# Peripheral_Connections.net
KiCad netlist of a schematic drawn in Altium Designer
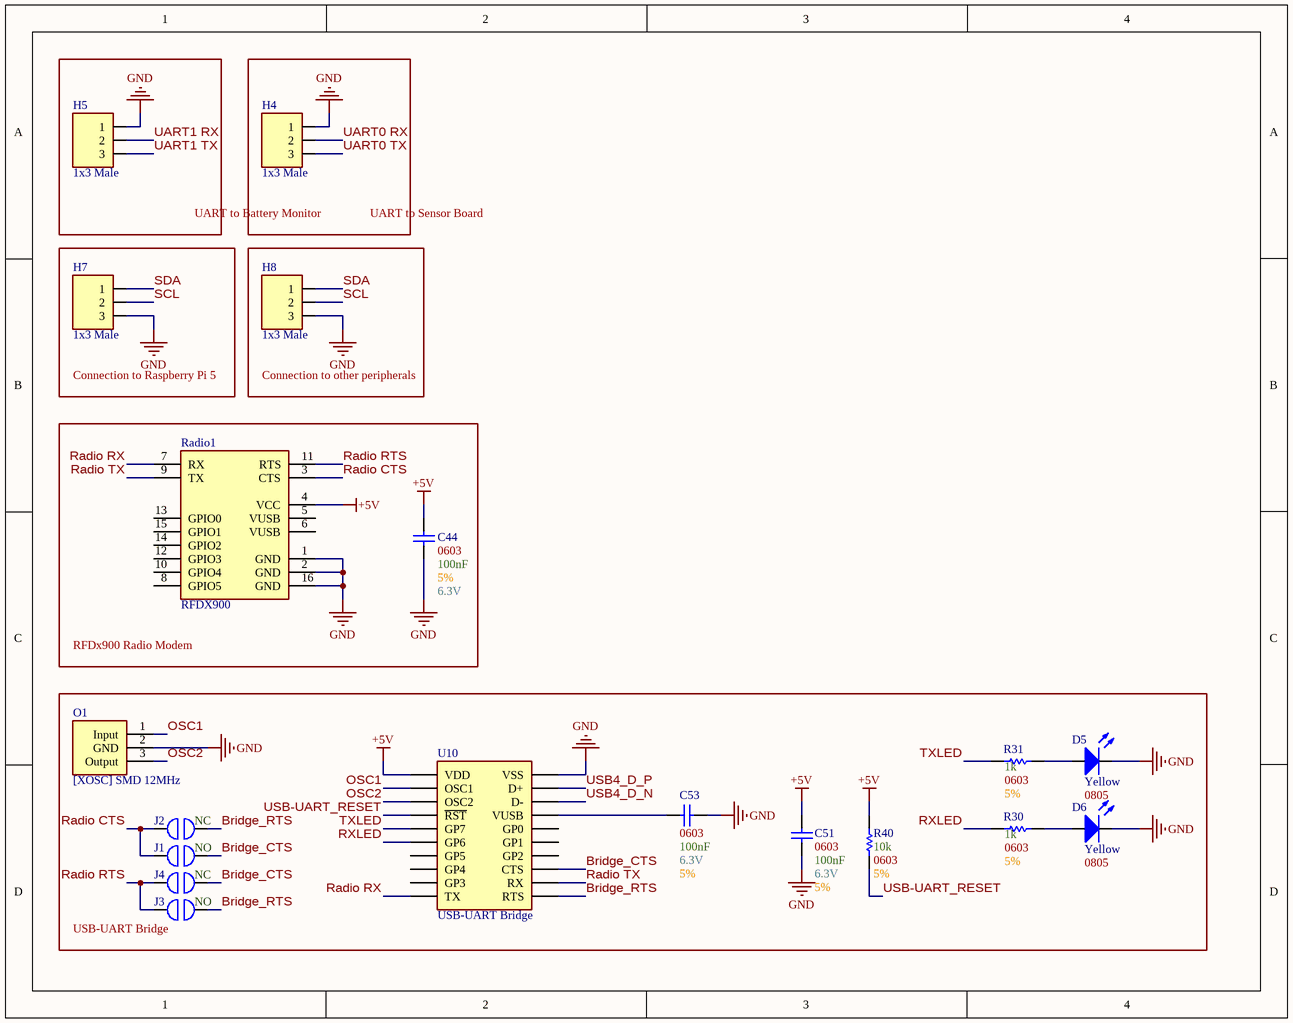
[diagram p0: Peripheral Connections.SchDoc]

(export (version "E")
  (design (tool "Eeschema 10.0.6"))
  (components
    (comp (ref "C44")
      (value "[Cap] SMD Nonpolarized")
      (footprint "[Cap] SMD 0603")
      (fields
        (field (name "SIZE PACKAGE") "0603")
        (field (name "CAPACITANCE") "100nF")
        (field (name "VOLTAGE") "6.3V")
        (field (name "TOLERANCE") "5%")
      )
      (libsource (lib "RADM Components") (part "[Cap] SMD Nonpolarized"))
    )
    (comp (ref "C51")
      (value "[Cap] SMD Nonpolarized")
      (footprint "[Cap] SMD 0603")
      (fields
        (field (name "SIZE PACKAGE") "0603")
        (field (name "CAPACITANCE") "100nF")
        (field (name "VOLTAGE") "6.3V")
        (field (name "TOLERANCE") "5%")
      )
      (libsource (lib "RADM Components") (part "[Cap] SMD Nonpolarized"))
    )
    (comp (ref "C53")
      (value "[Cap] SMD Nonpolarized")
      (footprint "[Cap] SMD 0603")
      (fields
        (field (name "SIZE PACKAGE") "0603")
        (field (name "CAPACITANCE") "100nF")
        (field (name "VOLTAGE") "6.3V")
        (field (name "TOLERANCE") "5%")
      )
      (libsource (lib "RADM Components") (part "[Cap] SMD Nonpolarized"))
    )
    (comp (ref "D5")
      (value "SMD LED")
      (footprint "[LED] SMD 0805")
      (description "Generic")
      (fields (field (name "COLOR") "Yellow") (field (name "SIZE PACKAGE") "0805"))
      (libsource (lib "RADM Components") (part "[LED] SMD"))
    )
    (comp (ref "D6")
      (value "SMD LED")
      (footprint "[LED] SMD 0805")
      (description "Generic")
      (fields (field (name "COLOR") "Yellow") (field (name "SIZE PACKAGE") "0805"))
      (libsource (lib "RADM Components") (part "[LED] SMD"))
    )
    (comp (ref "H4")
      (value "1x3 Male")
      (footprint "[Header] Shrouded 1x3 Male")
      (description "070543-0037\r\nMates with 005057-9403")
      (libsource (lib "RADM Connectors") (part "[Header] Shrouded 1x3 Male"))
    )
    (comp (ref "H5")
      (value "1x3 Male")
      (footprint "[Header] Shrouded 1x3 Male")
      (description "070543-0037\r\nMates with 005057-9403")
      (libsource (lib "RADM Connectors") (part "[Header] Shrouded 1x3 Male"))
    )
    (comp (ref "H7")
      (value "1x3 Male")
      (footprint "[Header] Shrouded 1x3 Male")
      (description "070543-0037\r\nMates with 005057-9403")
      (libsource (lib "RADM Connectors") (part "[Header] Shrouded 1x3 Male"))
    )
    (comp (ref "H8")
      (value "1x3 Male")
      (footprint "[Header] Shrouded 1x3 Male")
      (description "070543-0037\r\nMates with 005057-9403")
      (libsource (lib "RADM Connectors") (part "[Header] Shrouded 1x3 Male"))
    )
    (comp (ref "J1")
      (value "[Jump] SMD Jumper")
      (footprint "[Jumper] Solderable Jumper")
      (description "Solderable jumper")
      (fields (field (name "NO/NC") "NO"))
      (libsource (lib "RADM Components") (part "[Jump] SMD Jumper"))
    )
    (comp (ref "J2")
      (value "[Jump] SMD Jumper")
      (footprint "[Jumper] Solderable Jumper")
      (description "Solderable jumper")
      (fields (field (name "NO/NC") "NC"))
      (libsource (lib "RADM Components") (part "[Jump] SMD Jumper"))
    )
    (comp (ref "J3")
      (value "[Jump] SMD Jumper")
      (footprint "[Jumper] Solderable Jumper")
      (description "Solderable jumper")
      (fields (field (name "NO/NC") "NO"))
      (libsource (lib "RADM Components") (part "[Jump] SMD Jumper"))
    )
    (comp (ref "J4")
      (value "[Jump] SMD Jumper")
      (footprint "[Jumper] Solderable Jumper")
      (description "Solderable jumper")
      (fields (field (name "NO/NC") "NC"))
      (libsource (lib "RADM Components") (part "[Jump] SMD Jumper"))
    )
    (comp (ref "O1")
      (value "[XOSC] SMD 12MHz")
      (footprint "[XOSC] SMD 12MHz")
      (libsource (lib "RADM Components") (part "[XOSC] SMD 12MHz"))
    )
    (comp (ref "R30")
      (value "[Res] SMD Resistor")
      (footprint "[Res] SMD 0603")
      (description "Generic")
      (fields
        (field (name "RESISTANCE") "1k")
        (field (name "SIZE PACKAGE") "0603")
        (field (name "TOLERANCE") "5%")
      )
      (libsource (lib "RADM Components") (part "[Res] SMD Resistor"))
    )
    (comp (ref "R31")
      (value "[Res] SMD Resistor")
      (footprint "[Res] SMD 0603")
      (description "Generic")
      (fields
        (field (name "RESISTANCE") "1k")
        (field (name "SIZE PACKAGE") "0603")
        (field (name "TOLERANCE") "5%")
      )
      (libsource (lib "RADM Components") (part "[Res] SMD Resistor"))
    )
    (comp (ref "R40")
      (value "[Res] SMD Resistor")
      (footprint "[Res] SMD 0603")
      (description "Generic")
      (fields
        (field (name "RESISTANCE") "10k")
        (field (name "SIZE PACKAGE") "0603")
        (field (name "TOLERANCE") "5%")
      )
      (libsource (lib "RADM Components") (part "[Res] SMD Resistor"))
    )
    (comp (ref "Radio1")
      (value "RFDX900")
      (footprint "[Device] RFDX900 Radio SMD Mount")
      (description "RFDX900 Long-Range RF Module")
      (libsource (lib "RADM Components") (part "[Device] RFDX900 Radio"))
    )
    (comp (ref "U10")
      (value "USB-UART Bridge")
      (footprint "[IC] USB-UART Bridge")
      (description "MCP2200T-I/SO")
      (libsource (lib "RADM Components") (part "[IC] USB-UART Bridge"))
    )
  )
  (nets
    (net (code "1") (name "+5V") (class "Default")
      (node (ref "C44") (pin "2") (pinfunction "2_2") (pintype "passive"))
      (node (ref "C51") (pin "2") (pinfunction "2_2") (pintype "passive"))
      (node (ref "R40") (pin "2") (pinfunction "2_2") (pintype "passive"))
      (node (ref "Radio1") (pin "4") (pinfunction "VCC_4") (pintype "passive"))
      (node (ref "U10") (pin "1") (pinfunction "VDD_1") (pintype "passive"))
    )
    (net (code "2") (name "/Bridge_CTS") (class "Default")
      (node (ref "J1") (pin "2") (pintype "passive"))
      (node (ref "J4") (pin "2") (pintype "passive"))
      (node (ref "U10") (pin "13") (pinfunction "CTS_13") (pintype "passive"))
    )
    (net (code "3") (name "/Bridge_RTS") (class "Default")
      (node (ref "J2") (pin "2") (pintype "passive"))
      (node (ref "J3") (pin "2") (pintype "passive"))
      (node (ref "U10") (pin "11") (pinfunction "RTS_11") (pintype "passive"))
    )
    (net (code "4") (name "/OSC1") (class "Default")
      (node (ref "O1") (pin "1") (pinfunction "Input_1") (pintype "passive"))
      (node (ref "U10") (pin "2") (pinfunction "OSC1_2") (pintype "passive"))
    )
    (net (code "5") (name "/OSC2") (class "Default")
      (node (ref "O1") (pin "3") (pinfunction "Output_3") (pintype "passive"))
      (node (ref "U10") (pin "3") (pinfunction "OSC2_3") (pintype "passive"))
    )
    (net (code "6") (name "/RXLED") (class "Default")
      (node (ref "R30") (pin "2") (pinfunction "2_2") (pintype "passive"))
      (node (ref "U10") (pin "6") (pinfunction "GP6_6") (pintype "passive"))
    )
    (net (code "7") (name "/Radio CTS") (class "Default")
      (node (ref "J1") (pin "1") (pintype "passive"))
      (node (ref "J2") (pin "1") (pintype "passive"))
      (node (ref "Radio1") (pin "3") (pinfunction "CTS_3") (pintype "passive"))
    )
    (net (code "8") (name "/Radio RTS") (class "Default")
      (node (ref "J3") (pin "1") (pintype "passive"))
      (node (ref "J4") (pin "1") (pintype "passive"))
      (node (ref "Radio1") (pin "11") (pinfunction "RTS_11") (pintype "passive"))
    )
    (net (code "9") (name "/Radio RX") (class "Default")
      (node (ref "Radio1") (pin "7") (pinfunction "RX_7") (pintype "passive"))
      (node (ref "U10") (pin "10") (pinfunction "TX_10") (pintype "passive"))
    )
    (net (code "10") (name "/Radio TX") (class "Default")
      (node (ref "Radio1") (pin "9") (pinfunction "TX_9") (pintype "passive"))
      (node (ref "U10") (pin "12") (pinfunction "RX_12") (pintype "passive"))
    )
    (net (code "11") (name "/SCL") (class "Default")
      (node (ref "H7") (pin "2") (pinfunction "2_2") (pintype "passive"))
      (node (ref "H8") (pin "2") (pinfunction "2_2") (pintype "passive"))
    )
    (net (code "12") (name "/SDA") (class "Default")
      (node (ref "H7") (pin "1") (pinfunction "1_1") (pintype "passive"))
      (node (ref "H8") (pin "1") (pinfunction "1_1") (pintype "passive"))
    )
    (net (code "13") (name "/TXLED") (class "Default")
      (node (ref "R31") (pin "2") (pinfunction "2_2") (pintype "passive"))
      (node (ref "U10") (pin "5") (pinfunction "GP7_5") (pintype "passive"))
    )
    (net (code "14") (name "/UART0 RX") (class "Default")
      (node (ref "H4") (pin "2") (pinfunction "2_2") (pintype "passive"))
    )
    (net (code "15") (name "/UART0 TX") (class "Default")
      (node (ref "H4") (pin "3") (pinfunction "3_3") (pintype "passive"))
    )
    (net (code "16") (name "/UART1 RX") (class "Default")
      (node (ref "H5") (pin "2") (pinfunction "2_2") (pintype "passive"))
    )
    (net (code "17") (name "/UART1 TX") (class "Default")
      (node (ref "H5") (pin "3") (pinfunction "3_3") (pintype "passive"))
    )
    (net (code "18") (name "/USB-UART_RESET") (class "Default")
      (node (ref "R40") (pin "1") (pinfunction "1_1") (pintype "passive"))
      (node (ref "U10") (pin "4") (pinfunction "RST_4") (pintype "passive"))
    )
    (net (code "19") (name "/USB4_D_N") (class "Default")
      (node (ref "U10") (pin "18") (pinfunction "D-_18") (pintype "passive"))
    )
    (net (code "20") (name "/USB4_D_P") (class "Default")
      (node (ref "U10") (pin "19") (pinfunction "D+_19") (pintype "passive"))
    )
    (net (code "21") (name "GND") (class "Default")
      (node (ref "C44") (pin "1") (pinfunction "1_1") (pintype "passive"))
      (node (ref "C51") (pin "1") (pinfunction "1_1") (pintype "passive"))
      (node (ref "C53") (pin "1") (pinfunction "1_1") (pintype "passive"))
      (node (ref "D5") (pin "2") (pinfunction "Cathode_2") (pintype "passive"))
      (node (ref "D6") (pin "2") (pinfunction "Cathode_2") (pintype "passive"))
      (node (ref "H4") (pin "1") (pinfunction "1_1") (pintype "passive"))
      (node (ref "H5") (pin "1") (pinfunction "1_1") (pintype "passive"))
      (node (ref "H7") (pin "3") (pinfunction "3_3") (pintype "passive"))
      (node (ref "H8") (pin "3") (pinfunction "3_3") (pintype "passive"))
      (node (ref "O1") (pin "2") (pinfunction "GND_2") (pintype "passive"))
      (node (ref "Radio1") (pin "1") (pinfunction "GND_1") (pintype "passive"))
      (node (ref "Radio1") (pin "16") (pinfunction "GND_16") (pintype "passive"))
      (node (ref "Radio1") (pin "2") (pinfunction "GND_2") (pintype "passive"))
      (node (ref "U10") (pin "20") (pinfunction "VSS_20") (pintype "passive"))
    )
    (net (code "22") (name "Net-(D5-Anode)") (class "Default")
      (node (ref "D5") (pin "1") (pinfunction "Anode_1") (pintype "passive"))
      (node (ref "R31") (pin "1") (pinfunction "1_1") (pintype "passive"))
    )
    (net (code "23") (name "Net-(D6-Anode)") (class "Default")
      (node (ref "D6") (pin "1") (pinfunction "Anode_1") (pintype "passive"))
      (node (ref "R30") (pin "1") (pinfunction "1_1") (pintype "passive"))
    )
    (net (code "24") (name "Net-(U10-VUSB)") (class "Default")
      (node (ref "C53") (pin "2") (pinfunction "2_2") (pintype "passive"))
      (node (ref "U10") (pin "17") (pinfunction "VUSB_17") (pintype "passive"))
    )
    (net (code "25") (name "unconnected-(Radio1-GPIO0-Pad13)") (class "Default")
      (node (ref "Radio1") (pin "13") (pinfunction "GPIO0_13") (pintype "passive"))
    )
    (net (code "26") (name "unconnected-(Radio1-GPIO1-Pad15)") (class "Default")
      (node (ref "Radio1") (pin "15") (pinfunction "GPIO1_15") (pintype "passive"))
    )
    (net (code "27") (name "unconnected-(Radio1-GPIO2-Pad14)") (class "Default")
      (node (ref "Radio1") (pin "14") (pinfunction "GPIO2_14") (pintype "passive"))
    )
    (net (code "28") (name "unconnected-(Radio1-GPIO3-Pad12)") (class "Default")
      (node (ref "Radio1") (pin "12") (pinfunction "GPIO3_12") (pintype "passive"))
    )
    (net (code "29") (name "unconnected-(Radio1-GPIO4-Pad10)") (class "Default")
      (node (ref "Radio1") (pin "10") (pinfunction "GPIO4_10") (pintype "passive"))
    )
    (net (code "30") (name "unconnected-(Radio1-GPIO5-Pad8)") (class "Default")
      (node (ref "Radio1") (pin "8") (pinfunction "GPIO5_8") (pintype "passive"))
    )
    (net (code "31") (name "unconnected-(Radio1-VUSB-Pad5)") (class "Default")
      (node (ref "Radio1") (pin "5") (pinfunction "VUSB_5") (pintype "passive"))
    )
    (net (code "32") (name "unconnected-(Radio1-VUSB-Pad6)") (class "Default")
      (node (ref "Radio1") (pin "6") (pinfunction "VUSB_6") (pintype "passive"))
    )
    (net (code "33") (name "unconnected-(U10-GP0-Pad16)") (class "Default")
      (node (ref "U10") (pin "16") (pinfunction "GP0_16") (pintype "passive"))
    )
    (net (code "34") (name "unconnected-(U10-GP1-Pad15)") (class "Default")
      (node (ref "U10") (pin "15") (pinfunction "GP1_15") (pintype "passive"))
    )
    (net (code "35") (name "unconnected-(U10-GP2-Pad14)") (class "Default")
      (node (ref "U10") (pin "14") (pinfunction "GP2_14") (pintype "passive"))
    )
    (net (code "36") (name "unconnected-(U10-GP3-Pad9)") (class "Default")
      (node (ref "U10") (pin "9") (pinfunction "GP3_9") (pintype "passive"))
    )
    (net (code "37") (name "unconnected-(U10-GP4-Pad8)") (class "Default")
      (node (ref "U10") (pin "8") (pinfunction "GP4_8") (pintype "passive"))
    )
    (net (code "38") (name "unconnected-(U10-GP5-Pad7)") (class "Default")
      (node (ref "U10") (pin "7") (pinfunction "GP5_7") (pintype "passive"))
    )
  )
)
